# FPGA_PWR.net
KiCad netlist of a schematic drawn in Altium Designer
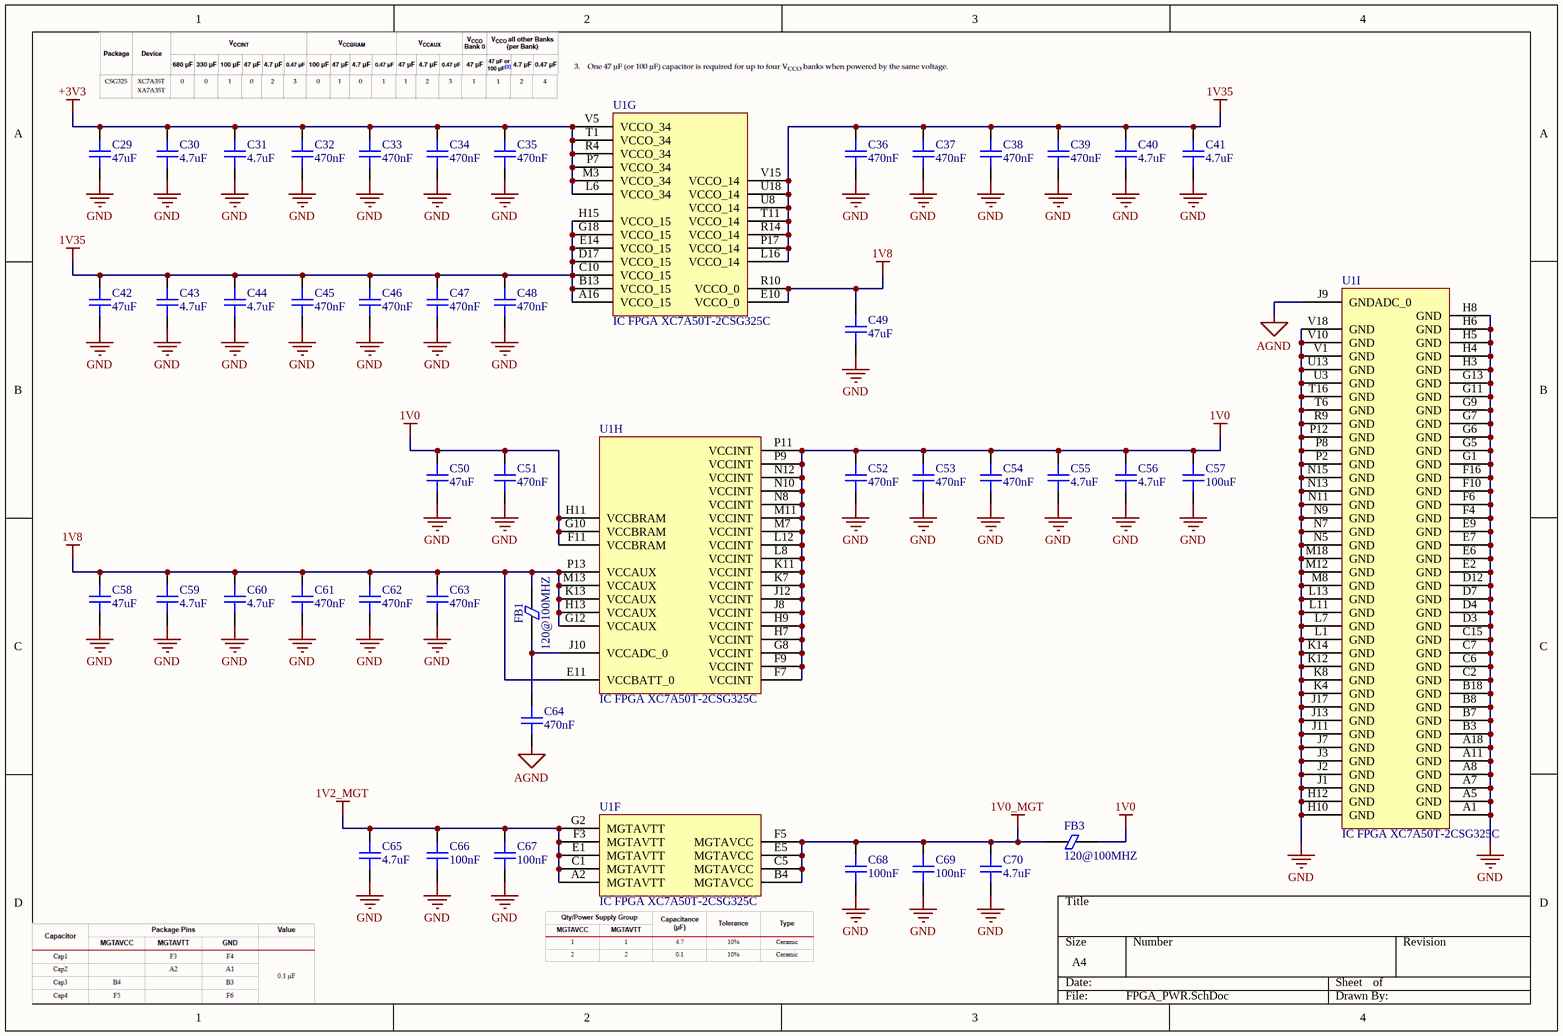
[diagram p0: FPGA_PWR.SchDoc]

(export (version "E")
  (design (tool "Eeschema 10.0.6"))
  (components
    (comp (ref "C29")
      (value "47uF")
      (footprint "GEN_C_0805")
      (fields
        (field (name "HOUSE PART NUMBER") "C-47uF-0805-002")
        (field (name "MANUFACTURER") "Samsung")
        (field (name "MANUFACTURER PART NUMBER") "CL21A476MQYNNNE")
      )
      (libsource (lib "DSO") (part "CAP 47uF 6.3V X5R 0805"))
    )
    (comp (ref "C30")
      (value "4.7uF")
      (footprint "GEN_C_0402")
      (fields
        (field (name "HOUSE PART NUMBER") "C-4.7uF-0402-002")
        (field (name "MANUFACTURER") "Murata")
        (field (name "MANUFACTURER PART NUMBER") "GRM155R60J475ME47D")
      )
      (libsource (lib "DSO") (part "CAP 4.7uF 6.3V X5R 0402"))
    )
    (comp (ref "C31")
      (value "4.7uF")
      (footprint "GEN_C_0402")
      (fields
        (field (name "HOUSE PART NUMBER") "C-4.7uF-0402-002")
        (field (name "MANUFACTURER") "Murata")
        (field (name "MANUFACTURER PART NUMBER") "GRM155R60J475ME47D")
      )
      (libsource (lib "DSO") (part "CAP 4.7uF 6.3V X5R 0402"))
    )
    (comp (ref "C32")
      (value "470nF")
      (footprint "GEN_C_0201")
      (fields
        (field (name "HOUSE PART NUMBER") "C-470nF-0201-002")
        (field (name "MANUFACTURER") "Murata")
        (field (name "MANUFACTURER PART NUMBER") "GRM033R60J474KE90D")
      )
      (libsource (lib "DSO") (part "CAP 470nF 6.3V X5R 0201"))
    )
    (comp (ref "C33")
      (value "470nF")
      (footprint "GEN_C_0201")
      (fields
        (field (name "HOUSE PART NUMBER") "C-470nF-0201-002")
        (field (name "MANUFACTURER") "Murata")
        (field (name "MANUFACTURER PART NUMBER") "GRM033R60J474KE90D")
      )
      (libsource (lib "DSO") (part "CAP 470nF 6.3V X5R 0201"))
    )
    (comp (ref "C34")
      (value "470nF")
      (footprint "GEN_C_0201")
      (fields
        (field (name "HOUSE PART NUMBER") "C-470nF-0201-002")
        (field (name "MANUFACTURER") "Murata")
        (field (name "MANUFACTURER PART NUMBER") "GRM033R60J474KE90D")
      )
      (libsource (lib "DSO") (part "CAP 470nF 6.3V X5R 0201"))
    )
    (comp (ref "C35")
      (value "470nF")
      (footprint "GEN_C_0201")
      (fields
        (field (name "HOUSE PART NUMBER") "C-470nF-0201-002")
        (field (name "MANUFACTURER") "Murata")
        (field (name "MANUFACTURER PART NUMBER") "GRM033R60J474KE90D")
      )
      (libsource (lib "DSO") (part "CAP 470nF 6.3V X5R 0201"))
    )
    (comp (ref "C36")
      (value "470nF")
      (footprint "GEN_C_0201")
      (fields
        (field (name "HOUSE PART NUMBER") "C-470nF-0201-002")
        (field (name "MANUFACTURER") "Murata")
        (field (name "MANUFACTURER PART NUMBER") "GRM033R60J474KE90D")
      )
      (libsource (lib "DSO") (part "CAP 470nF 6.3V X5R 0201"))
    )
    (comp (ref "C37")
      (value "470nF")
      (footprint "GEN_C_0201")
      (fields
        (field (name "HOUSE PART NUMBER") "C-470nF-0201-002")
        (field (name "MANUFACTURER") "Murata")
        (field (name "MANUFACTURER PART NUMBER") "GRM033R60J474KE90D")
      )
      (libsource (lib "DSO") (part "CAP 470nF 6.3V X5R 0201"))
    )
    (comp (ref "C38")
      (value "470nF")
      (footprint "GEN_C_0201")
      (fields
        (field (name "HOUSE PART NUMBER") "C-470nF-0201-002")
        (field (name "MANUFACTURER") "Murata")
        (field (name "MANUFACTURER PART NUMBER") "GRM033R60J474KE90D")
      )
      (libsource (lib "DSO") (part "CAP 470nF 6.3V X5R 0201"))
    )
    (comp (ref "C39")
      (value "470nF")
      (footprint "GEN_C_0201")
      (fields
        (field (name "HOUSE PART NUMBER") "C-470nF-0201-002")
        (field (name "MANUFACTURER") "Murata")
        (field (name "MANUFACTURER PART NUMBER") "GRM033R60J474KE90D")
      )
      (libsource (lib "DSO") (part "CAP 470nF 6.3V X5R 0201"))
    )
    (comp (ref "C40")
      (value "4.7uF")
      (footprint "GEN_C_0402")
      (fields
        (field (name "HOUSE PART NUMBER") "C-4.7uF-0402-002")
        (field (name "MANUFACTURER") "Murata")
        (field (name "MANUFACTURER PART NUMBER") "GRM155R60J475ME47D")
      )
      (libsource (lib "DSO") (part "CAP 4.7uF 6.3V X5R 0402"))
    )
    (comp (ref "C41")
      (value "4.7uF")
      (footprint "GEN_C_0402")
      (fields
        (field (name "HOUSE PART NUMBER") "C-4.7uF-0402-002")
        (field (name "MANUFACTURER") "Murata")
        (field (name "MANUFACTURER PART NUMBER") "GRM155R60J475ME47D")
      )
      (libsource (lib "DSO") (part "CAP 4.7uF 6.3V X5R 0402"))
    )
    (comp (ref "C42")
      (value "47uF")
      (footprint "GEN_C_0805")
      (fields
        (field (name "HOUSE PART NUMBER") "C-47uF-0805-002")
        (field (name "MANUFACTURER") "Samsung")
        (field (name "MANUFACTURER PART NUMBER") "CL21A476MQYNNNE")
      )
      (libsource (lib "DSO") (part "CAP 47uF 6.3V X5R 0805"))
    )
    (comp (ref "C43")
      (value "4.7uF")
      (footprint "GEN_C_0402")
      (fields
        (field (name "HOUSE PART NUMBER") "C-4.7uF-0402-002")
        (field (name "MANUFACTURER") "Murata")
        (field (name "MANUFACTURER PART NUMBER") "GRM155R60J475ME47D")
      )
      (libsource (lib "DSO") (part "CAP 4.7uF 6.3V X5R 0402"))
    )
    (comp (ref "C44")
      (value "4.7uF")
      (footprint "GEN_C_0402")
      (fields
        (field (name "HOUSE PART NUMBER") "C-4.7uF-0402-002")
        (field (name "MANUFACTURER") "Murata")
        (field (name "MANUFACTURER PART NUMBER") "GRM155R60J475ME47D")
      )
      (libsource (lib "DSO") (part "CAP 4.7uF 6.3V X5R 0402"))
    )
    (comp (ref "C45")
      (value "470nF")
      (footprint "GEN_C_0201")
      (fields
        (field (name "HOUSE PART NUMBER") "C-470nF-0201-002")
        (field (name "MANUFACTURER") "Murata")
        (field (name "MANUFACTURER PART NUMBER") "GRM033R60J474KE90D")
      )
      (libsource (lib "DSO") (part "CAP 470nF 6.3V X5R 0201"))
    )
    (comp (ref "C46")
      (value "470nF")
      (footprint "GEN_C_0201")
      (fields
        (field (name "HOUSE PART NUMBER") "C-470nF-0201-002")
        (field (name "MANUFACTURER") "Murata")
        (field (name "MANUFACTURER PART NUMBER") "GRM033R60J474KE90D")
      )
      (libsource (lib "DSO") (part "CAP 470nF 6.3V X5R 0201"))
    )
    (comp (ref "C47")
      (value "470nF")
      (footprint "GEN_C_0201")
      (fields
        (field (name "HOUSE PART NUMBER") "C-470nF-0201-002")
        (field (name "MANUFACTURER") "Murata")
        (field (name "MANUFACTURER PART NUMBER") "GRM033R60J474KE90D")
      )
      (libsource (lib "DSO") (part "CAP 470nF 6.3V X5R 0201"))
    )
    (comp (ref "C48")
      (value "470nF")
      (footprint "GEN_C_0201")
      (fields
        (field (name "HOUSE PART NUMBER") "C-470nF-0201-002")
        (field (name "MANUFACTURER") "Murata")
        (field (name "MANUFACTURER PART NUMBER") "GRM033R60J474KE90D")
      )
      (libsource (lib "DSO") (part "CAP 470nF 6.3V X5R 0201"))
    )
    (comp (ref "C49")
      (value "47uF")
      (footprint "GEN_C_0805")
      (fields
        (field (name "HOUSE PART NUMBER") "C-47uF-0805-002")
        (field (name "MANUFACTURER") "Samsung")
        (field (name "MANUFACTURER PART NUMBER") "CL21A476MQYNNNE")
      )
      (libsource (lib "DSO") (part "CAP 47uF 6.3V X5R 0805"))
    )
    (comp (ref "C50")
      (value "47uF")
      (footprint "GEN_C_0805")
      (fields
        (field (name "HOUSE PART NUMBER") "C-47uF-0805-002")
        (field (name "MANUFACTURER") "Samsung")
        (field (name "MANUFACTURER PART NUMBER") "CL21A476MQYNNNE")
      )
      (libsource (lib "DSO") (part "CAP 47uF 6.3V X5R 0805"))
    )
    (comp (ref "C51")
      (value "470nF")
      (footprint "GEN_C_0201")
      (fields
        (field (name "HOUSE PART NUMBER") "C-470nF-0201-002")
        (field (name "MANUFACTURER") "Murata")
        (field (name "MANUFACTURER PART NUMBER") "GRM033R60J474KE90D")
      )
      (libsource (lib "DSO") (part "CAP 470nF 6.3V X5R 0201"))
    )
    (comp (ref "C52")
      (value "470nF")
      (footprint "GEN_C_0201")
      (fields
        (field (name "HOUSE PART NUMBER") "C-470nF-0201-002")
        (field (name "MANUFACTURER") "Murata")
        (field (name "MANUFACTURER PART NUMBER") "GRM033R60J474KE90D")
      )
      (libsource (lib "DSO") (part "CAP 470nF 6.3V X5R 0201"))
    )
    (comp (ref "C53")
      (value "470nF")
      (footprint "GEN_C_0201")
      (fields
        (field (name "HOUSE PART NUMBER") "C-470nF-0201-002")
        (field (name "MANUFACTURER") "Murata")
        (field (name "MANUFACTURER PART NUMBER") "GRM033R60J474KE90D")
      )
      (libsource (lib "DSO") (part "CAP 470nF 6.3V X5R 0201"))
    )
    (comp (ref "C54")
      (value "470nF")
      (footprint "GEN_C_0201")
      (fields
        (field (name "HOUSE PART NUMBER") "C-470nF-0201-002")
        (field (name "MANUFACTURER") "Murata")
        (field (name "MANUFACTURER PART NUMBER") "GRM033R60J474KE90D")
      )
      (libsource (lib "DSO") (part "CAP 470nF 6.3V X5R 0201"))
    )
    (comp (ref "C55")
      (value "4.7uF")
      (footprint "GEN_C_0402")
      (fields
        (field (name "HOUSE PART NUMBER") "C-4.7uF-0402-002")
        (field (name "MANUFACTURER") "Murata")
        (field (name "MANUFACTURER PART NUMBER") "GRM155R60J475ME47D")
      )
      (libsource (lib "DSO") (part "CAP 4.7uF 6.3V X5R 0402"))
    )
    (comp (ref "C56")
      (value "4.7uF")
      (footprint "GEN_C_0402")
      (fields
        (field (name "HOUSE PART NUMBER") "C-4.7uF-0402-002")
        (field (name "MANUFACTURER") "Murata")
        (field (name "MANUFACTURER PART NUMBER") "GRM155R60J475ME47D")
      )
      (libsource (lib "DSO") (part "CAP 4.7uF 6.3V X5R 0402"))
    )
    (comp (ref "C57")
      (value "100uF")
      (footprint "GEN_C_1210")
      (fields
        (field (name "HOUSE PART NUMBER") "C-100uF-1210-002")
        (field (name "MANUFACTURER") "Samsung")
        (field (name "MANUFACTURER PART NUMBER") "CL32A107MQVNNNE")
      )
      (libsource (lib "DSO") (part "CAP 100uF 6.3V X5R 1210"))
    )
    (comp (ref "C58")
      (value "47uF")
      (footprint "GEN_C_0805")
      (fields
        (field (name "HOUSE PART NUMBER") "C-47uF-0805-002")
        (field (name "MANUFACTURER") "Samsung")
        (field (name "MANUFACTURER PART NUMBER") "CL21A476MQYNNNE")
      )
      (libsource (lib "DSO") (part "CAP 47uF 6.3V X5R 0805"))
    )
    (comp (ref "C59")
      (value "4.7uF")
      (footprint "GEN_C_0402")
      (fields
        (field (name "HOUSE PART NUMBER") "C-4.7uF-0402-002")
        (field (name "MANUFACTURER") "Murata")
        (field (name "MANUFACTURER PART NUMBER") "GRM155R60J475ME47D")
      )
      (libsource (lib "DSO") (part "CAP 4.7uF 6.3V X5R 0402"))
    )
    (comp (ref "C60")
      (value "4.7uF")
      (footprint "GEN_C_0402")
      (fields
        (field (name "HOUSE PART NUMBER") "C-4.7uF-0402-002")
        (field (name "MANUFACTURER") "Murata")
        (field (name "MANUFACTURER PART NUMBER") "GRM155R60J475ME47D")
      )
      (libsource (lib "DSO") (part "CAP 4.7uF 6.3V X5R 0402"))
    )
    (comp (ref "C61")
      (value "470nF")
      (footprint "GEN_C_0201")
      (fields
        (field (name "HOUSE PART NUMBER") "C-470nF-0201-002")
        (field (name "MANUFACTURER") "Murata")
        (field (name "MANUFACTURER PART NUMBER") "GRM033R60J474KE90D")
      )
      (libsource (lib "DSO") (part "CAP 470nF 6.3V X5R 0201"))
    )
    (comp (ref "C62")
      (value "470nF")
      (footprint "GEN_C_0201")
      (fields
        (field (name "HOUSE PART NUMBER") "C-470nF-0201-002")
        (field (name "MANUFACTURER") "Murata")
        (field (name "MANUFACTURER PART NUMBER") "GRM033R60J474KE90D")
      )
      (libsource (lib "DSO") (part "CAP 470nF 6.3V X5R 0201"))
    )
    (comp (ref "C63")
      (value "470nF")
      (footprint "GEN_C_0201")
      (fields
        (field (name "HOUSE PART NUMBER") "C-470nF-0201-002")
        (field (name "MANUFACTURER") "Murata")
        (field (name "MANUFACTURER PART NUMBER") "GRM033R60J474KE90D")
      )
      (libsource (lib "DSO") (part "CAP 470nF 6.3V X5R 0201"))
    )
    (comp (ref "C64")
      (value "470nF")
      (footprint "GEN_C_0201")
      (fields
        (field (name "HOUSE PART NUMBER") "C-470nF-0201-002")
        (field (name "MANUFACTURER") "Murata")
        (field (name "MANUFACTURER PART NUMBER") "GRM033R60J474KE90D")
      )
      (libsource (lib "DSO") (part "CAP 470nF 6.3V X5R 0201"))
    )
    (comp (ref "C65")
      (value "4.7uF")
      (footprint "GEN_C_0402")
      (fields
        (field (name "HOUSE PART NUMBER") "C-4.7uF-0402-002")
        (field (name "MANUFACTURER") "Murata")
        (field (name "MANUFACTURER PART NUMBER") "GRM155R60J475ME47D")
      )
      (libsource (lib "DSO") (part "CAP 4.7uF 6.3V X5R 0402"))
    )
    (comp (ref "C66")
      (value "100nF")
      (footprint "GEN_C_0201")
      (fields
        (field (name "HOUSE PART NUMBER") "C-100nF-0201-002")
        (field (name "MANUFACTURER") "Murata")
        (field (name "MANUFACTURER PART NUMBER") "GRM033R60J104KE19D")
      )
      (libsource (lib "DSO") (part "CAP 100nF 6.3V X5R 0201"))
    )
    (comp (ref "C67")
      (value "100nF")
      (footprint "GEN_C_0201")
      (fields
        (field (name "HOUSE PART NUMBER") "C-100nF-0201-002")
        (field (name "MANUFACTURER") "Murata")
        (field (name "MANUFACTURER PART NUMBER") "GRM033R60J104KE19D")
      )
      (libsource (lib "DSO") (part "CAP 100nF 6.3V X5R 0201"))
    )
    (comp (ref "C68")
      (value "100nF")
      (footprint "GEN_C_0201")
      (fields
        (field (name "HOUSE PART NUMBER") "C-100nF-0201-002")
        (field (name "MANUFACTURER") "Murata")
        (field (name "MANUFACTURER PART NUMBER") "GRM033R60J104KE19D")
      )
      (libsource (lib "DSO") (part "CAP 100nF 6.3V X5R 0201"))
    )
    (comp (ref "C69")
      (value "100nF")
      (footprint "GEN_C_0201")
      (fields
        (field (name "HOUSE PART NUMBER") "C-100nF-0201-002")
        (field (name "MANUFACTURER") "Murata")
        (field (name "MANUFACTURER PART NUMBER") "GRM033R60J104KE19D")
      )
      (libsource (lib "DSO") (part "CAP 100nF 6.3V X5R 0201"))
    )
    (comp (ref "C70")
      (value "4.7uF")
      (footprint "GEN_C_0402")
      (fields
        (field (name "HOUSE PART NUMBER") "C-4.7uF-0402-002")
        (field (name "MANUFACTURER") "Murata")
        (field (name "MANUFACTURER PART NUMBER") "GRM155R60J475ME47D")
      )
      (libsource (lib "DSO") (part "CAP 4.7uF 6.3V X5R 0402"))
    )
    (comp (ref "FB1")
      (value "120@100MHZ")
      (footprint "GEN_R_0402")
      (fields (field (name "HOUSE PART NUMBER") "BLM15PX121SN1D") (field (name "MANUFACTURER") "Murata"))
      (libsource (lib "DSO") (part "FERRITE BEAD 120 OHM 0402"))
    )
    (comp (ref "FB3")
      (value "120@100MHZ")
      (footprint "GEN_R_0402")
      (fields (field (name "HOUSE PART NUMBER") "BLM15PX121SN1D") (field (name "MANUFACTURER") "Murata"))
      (libsource (lib "DSO") (part "FERRITE BEAD 120 OHM 0402"))
    )
    (comp (ref "U1")
      (value "IC FPGA XC7A50T-2CSG325C")
      (footprint "XILINX_XC7A50T-2CSG325C")
      (description "Artix-7 FPGA, 150 User I/Os, 4 GTP, 324-Ball BGA, Speed Grade 2, Commercial Grade, Pb-Free")
      (fields (field (name "MANUFACTURER") "Xilinx") (field (name "HOUSE PART NUMBER") "XC7A50T-2CSG325C"))
      (libsource (lib "DSO") (part "IC FPGA XC7A50T-2CSG325C"))
    )
  )
  (nets
    (net (code "1") (name "+3V3") (class "Default")
      (node (ref "C29") (pin "2") (pinfunction "2_2") (pintype "passive"))
      (node (ref "C30") (pin "2") (pinfunction "2_2") (pintype "passive"))
      (node (ref "C31") (pin "2") (pinfunction "2_2") (pintype "passive"))
      (node (ref "C32") (pin "2") (pinfunction "2_2") (pintype "passive"))
      (node (ref "C33") (pin "2") (pinfunction "2_2") (pintype "passive"))
      (node (ref "C34") (pin "2") (pinfunction "2_2") (pintype "passive"))
      (node (ref "C35") (pin "2") (pinfunction "2_2") (pintype "passive"))
      (node (ref "U1") (pin "L6") (pinfunction "VCCO_34_L6") (pintype "power_in"))
      (node (ref "U1") (pin "M3") (pinfunction "VCCO_34_M3") (pintype "power_in"))
      (node (ref "U1") (pin "P7") (pinfunction "VCCO_34_P7") (pintype "power_in"))
      (node (ref "U1") (pin "R4") (pinfunction "VCCO_34_R4") (pintype "power_in"))
      (node (ref "U1") (pin "T1") (pinfunction "VCCO_34_T1") (pintype "power_in"))
      (node (ref "U1") (pin "V5") (pinfunction "VCCO_34_V5") (pintype "power_in"))
    )
    (net (code "2") (name "1V0") (class "Default")
      (node (ref "C50") (pin "2") (pinfunction "2_2") (pintype "passive"))
      (node (ref "C51") (pin "2") (pinfunction "2_2") (pintype "passive"))
      (node (ref "C52") (pin "2") (pinfunction "2_2") (pintype "passive"))
      (node (ref "C53") (pin "2") (pinfunction "2_2") (pintype "passive"))
      (node (ref "C54") (pin "2") (pinfunction "2_2") (pintype "passive"))
      (node (ref "C55") (pin "2") (pinfunction "2_2") (pintype "passive"))
      (node (ref "C56") (pin "2") (pinfunction "2_2") (pintype "passive"))
      (node (ref "C57") (pin "2") (pinfunction "2_2") (pintype "passive"))
      (node (ref "FB3") (pin "1") (pinfunction "1_1") (pintype "passive"))
      (node (ref "U1") (pin "F11") (pinfunction "VCCBRAM_F11") (pintype "power_in"))
      (node (ref "U1") (pin "F7") (pinfunction "VCCINT_F7") (pintype "power_in"))
      (node (ref "U1") (pin "F9") (pinfunction "VCCINT_F9") (pintype "power_in"))
      (node (ref "U1") (pin "G10") (pinfunction "VCCBRAM_G10") (pintype "power_in"))
      (node (ref "U1") (pin "G8") (pinfunction "VCCINT_G8") (pintype "power_in"))
      (node (ref "U1") (pin "H11") (pinfunction "VCCBRAM_H11") (pintype "power_in"))
      (node (ref "U1") (pin "H7") (pinfunction "VCCINT_H7") (pintype "power_in"))
      (node (ref "U1") (pin "H9") (pinfunction "VCCINT_H9") (pintype "power_in"))
      (node (ref "U1") (pin "J12") (pinfunction "VCCINT_J12") (pintype "power_in"))
      (node (ref "U1") (pin "J8") (pinfunction "VCCINT_J8") (pintype "power_in"))
      (node (ref "U1") (pin "K11") (pinfunction "VCCINT_K11") (pintype "power_in"))
      (node (ref "U1") (pin "K7") (pinfunction "VCCINT_K7") (pintype "power_in"))
      (node (ref "U1") (pin "L12") (pinfunction "VCCINT_L12") (pintype "power_in"))
      (node (ref "U1") (pin "L8") (pinfunction "VCCINT_L8") (pintype "power_in"))
      (node (ref "U1") (pin "M11") (pinfunction "VCCINT_M11") (pintype "power_in"))
      (node (ref "U1") (pin "M7") (pinfunction "VCCINT_M7") (pintype "power_in"))
      (node (ref "U1") (pin "N10") (pinfunction "VCCINT_N10") (pintype "power_in"))
      (node (ref "U1") (pin "N12") (pinfunction "VCCINT_N12") (pintype "power_in"))
      (node (ref "U1") (pin "N8") (pinfunction "VCCINT_N8") (pintype "power_in"))
      (node (ref "U1") (pin "P11") (pinfunction "VCCINT_P11") (pintype "power_in"))
      (node (ref "U1") (pin "P9") (pinfunction "VCCINT_P9") (pintype "power_in"))
    )
    (net (code "3") (name "1V0_MGT") (class "Default")
      (node (ref "C68") (pin "2") (pinfunction "2_2") (pintype "passive"))
      (node (ref "C69") (pin "2") (pinfunction "2_2") (pintype "passive"))
      (node (ref "C70") (pin "2") (pinfunction "2_2") (pintype "passive"))
      (node (ref "FB3") (pin "2") (pinfunction "2_2") (pintype "passive"))
      (node (ref "U1") (pin "B4") (pinfunction "MGTAVCC_B4") (pintype "power_in"))
      (node (ref "U1") (pin "C5") (pinfunction "MGTAVCC_C5") (pintype "power_in"))
      (node (ref "U1") (pin "E5") (pinfunction "MGTAVCC_E5") (pintype "power_in"))
      (node (ref "U1") (pin "F5") (pinfunction "MGTAVCC_F5") (pintype "power_in"))
    )
    (net (code "4") (name "1V2_MGT") (class "Default")
      (node (ref "C65") (pin "2") (pinfunction "2_2") (pintype "passive"))
      (node (ref "C66") (pin "2") (pinfunction "2_2") (pintype "passive"))
      (node (ref "C67") (pin "2") (pinfunction "2_2") (pintype "passive"))
      (node (ref "U1") (pin "A2") (pinfunction "MGTAVTT_A2") (pintype "power_in"))
      (node (ref "U1") (pin "C1") (pinfunction "MGTAVTT_C1") (pintype "power_in"))
      (node (ref "U1") (pin "E1") (pinfunction "MGTAVTT_E1") (pintype "power_in"))
      (node (ref "U1") (pin "F3") (pinfunction "MGTAVTT_F3") (pintype "power_in"))
      (node (ref "U1") (pin "G2") (pinfunction "MGTAVTT_G2") (pintype "power_in"))
    )
    (net (code "5") (name "1V8") (class "Default")
      (node (ref "C49") (pin "2") (pinfunction "2_2") (pintype "passive"))
      (node (ref "C58") (pin "2") (pinfunction "2_2") (pintype "passive"))
      (node (ref "C59") (pin "2") (pinfunction "2_2") (pintype "passive"))
      (node (ref "C60") (pin "2") (pinfunction "2_2") (pintype "passive"))
      (node (ref "C61") (pin "2") (pinfunction "2_2") (pintype "passive"))
      (node (ref "C62") (pin "2") (pinfunction "2_2") (pintype "passive"))
      (node (ref "C63") (pin "2") (pinfunction "2_2") (pintype "passive"))
      (node (ref "FB1") (pin "2") (pinfunction "2_2") (pintype "passive"))
      (node (ref "U1") (pin "E10") (pinfunction "VCCO_0_E10") (pintype "power_in"))
      (node (ref "U1") (pin "E11") (pinfunction "VCCBATT_0_E11") (pintype "power_in"))
      (node (ref "U1") (pin "G12") (pinfunction "VCCAUX_G12") (pintype "power_in"))
      (node (ref "U1") (pin "H13") (pinfunction "VCCAUX_H13") (pintype "power_in"))
      (node (ref "U1") (pin "K13") (pinfunction "VCCAUX_K13") (pintype "power_in"))
      (node (ref "U1") (pin "M13") (pinfunction "VCCAUX_M13") (pintype "power_in"))
      (node (ref "U1") (pin "P13") (pinfunction "VCCAUX_P13") (pintype "power_in"))
      (node (ref "U1") (pin "R10") (pinfunction "VCCO_0_R10") (pintype "power_in"))
    )
    (net (code "6") (name "1V35") (class "Default")
      (node (ref "C36") (pin "2") (pinfunction "2_2") (pintype "passive"))
      (node (ref "C37") (pin "2") (pinfunction "2_2") (pintype "passive"))
      (node (ref "C38") (pin "2") (pinfunction "2_2") (pintype "passive"))
      (node (ref "C39") (pin "2") (pinfunction "2_2") (pintype "passive"))
      (node (ref "C40") (pin "2") (pinfunction "2_2") (pintype "passive"))
      (node (ref "C41") (pin "2") (pinfunction "2_2") (pintype "passive"))
      (node (ref "C42") (pin "2") (pinfunction "2_2") (pintype "passive"))
      (node (ref "C43") (pin "2") (pinfunction "2_2") (pintype "passive"))
      (node (ref "C44") (pin "2") (pinfunction "2_2") (pintype "passive"))
      (node (ref "C45") (pin "2") (pinfunction "2_2") (pintype "passive"))
      (node (ref "C46") (pin "2") (pinfunction "2_2") (pintype "passive"))
      (node (ref "C47") (pin "2") (pinfunction "2_2") (pintype "passive"))
      (node (ref "C48") (pin "2") (pinfunction "2_2") (pintype "passive"))
      (node (ref "U1") (pin "A16") (pinfunction "VCCO_15_A16") (pintype "power_in"))
      (node (ref "U1") (pin "B13") (pinfunction "VCCO_15_B13") (pintype "power_in"))
      (node (ref "U1") (pin "C10") (pinfunction "VCCO_15_C10") (pintype "power_in"))
      (node (ref "U1") (pin "D17") (pinfunction "VCCO_15_D17") (pintype "power_in"))
      (node (ref "U1") (pin "E14") (pinfunction "VCCO_15_E14") (pintype "power_in"))
      (node (ref "U1") (pin "G18") (pinfunction "VCCO_15_G18") (pintype "power_in"))
      (node (ref "U1") (pin "H15") (pinfunction "VCCO_15_H15") (pintype "power_in"))
      (node (ref "U1") (pin "L16") (pinfunction "VCCO_14_L16") (pintype "power_in"))
      (node (ref "U1") (pin "P17") (pinfunction "VCCO_14_P17") (pintype "power_in"))
      (node (ref "U1") (pin "R14") (pinfunction "VCCO_14_R14") (pintype "power_in"))
      (node (ref "U1") (pin "T11") (pinfunction "VCCO_14_T11") (pintype "power_in"))
      (node (ref "U1") (pin "U18") (pinfunction "VCCO_14_U18") (pintype "power_in"))
      (node (ref "U1") (pin "U8") (pinfunction "VCCO_14_U8") (pintype "power_in"))
      (node (ref "U1") (pin "V15") (pinfunction "VCCO_14_V15") (pintype "power_in"))
    )
    (net (code "7") (name "AGND") (class "Default")
      (node (ref "C64") (pin "1") (pinfunction "1_1") (pintype "passive"))
      (node (ref "U1") (pin "J9") (pinfunction "GNDADC_0_J9") (pintype "power_in"))
    )
    (net (code "8") (name "GND") (class "Default")
      (node (ref "C29") (pin "1") (pinfunction "1_1") (pintype "passive"))
      (node (ref "C30") (pin "1") (pinfunction "1_1") (pintype "passive"))
      (node (ref "C31") (pin "1") (pinfunction "1_1") (pintype "passive"))
      (node (ref "C32") (pin "1") (pinfunction "1_1") (pintype "passive"))
      (node (ref "C33") (pin "1") (pinfunction "1_1") (pintype "passive"))
      (node (ref "C34") (pin "1") (pinfunction "1_1") (pintype "passive"))
      (node (ref "C35") (pin "1") (pinfunction "1_1") (pintype "passive"))
      (node (ref "C36") (pin "1") (pinfunction "1_1") (pintype "passive"))
      (node (ref "C37") (pin "1") (pinfunction "1_1") (pintype "passive"))
      (node (ref "C38") (pin "1") (pinfunction "1_1") (pintype "passive"))
      (node (ref "C39") (pin "1") (pinfunction "1_1") (pintype "passive"))
      (node (ref "C40") (pin "1") (pinfunction "1_1") (pintype "passive"))
      (node (ref "C41") (pin "1") (pinfunction "1_1") (pintype "passive"))
      (node (ref "C42") (pin "1") (pinfunction "1_1") (pintype "passive"))
      (node (ref "C43") (pin "1") (pinfunction "1_1") (pintype "passive"))
      (node (ref "C44") (pin "1") (pinfunction "1_1") (pintype "passive"))
      (node (ref "C45") (pin "1") (pinfunction "1_1") (pintype "passive"))
      (node (ref "C46") (pin "1") (pinfunction "1_1") (pintype "passive"))
      (node (ref "C47") (pin "1") (pinfunction "1_1") (pintype "passive"))
      (node (ref "C48") (pin "1") (pinfunction "1_1") (pintype "passive"))
      (node (ref "C49") (pin "1") (pinfunction "1_1") (pintype "passive"))
      (node (ref "C50") (pin "1") (pinfunction "1_1") (pintype "passive"))
      (node (ref "C51") (pin "1") (pinfunction "1_1") (pintype "passive"))
      (node (ref "C52") (pin "1") (pinfunction "1_1") (pintype "passive"))
      (node (ref "C53") (pin "1") (pinfunction "1_1") (pintype "passive"))
      (node (ref "C54") (pin "1") (pinfunction "1_1") (pintype "passive"))
      (node (ref "C55") (pin "1") (pinfunction "1_1") (pintype "passive"))
      (node (ref "C56") (pin "1") (pinfunction "1_1") (pintype "passive"))
      (node (ref "C57") (pin "1") (pinfunction "1_1") (pintype "passive"))
      (node (ref "C58") (pin "1") (pinfunction "1_1") (pintype "passive"))
      (node (ref "C59") (pin "1") (pinfunction "1_1") (pintype "passive"))
      (node (ref "C60") (pin "1") (pinfunction "1_1") (pintype "passive"))
      (node (ref "C61") (pin "1") (pinfunction "1_1") (pintype "passive"))
      (node (ref "C62") (pin "1") (pinfunction "1_1") (pintype "passive"))
      (node (ref "C63") (pin "1") (pinfunction "1_1") (pintype "passive"))
      (node (ref "C65") (pin "1") (pinfunction "1_1") (pintype "passive"))
      (node (ref "C66") (pin "1") (pinfunction "1_1") (pintype "passive"))
      (node (ref "C67") (pin "1") (pinfunction "1_1") (pintype "passive"))
      (node (ref "C68") (pin "1") (pinfunction "1_1") (pintype "passive"))
      (node (ref "C69") (pin "1") (pinfunction "1_1") (pintype "passive"))
      (node (ref "C70") (pin "1") (pinfunction "1_1") (pintype "passive"))
      (node (ref "U1") (pin "A1") (pinfunction "GND_A1") (pintype "power_in"))
      (node (ref "U1") (pin "A11") (pinfunction "GND_A11") (pintype "power_in"))
      (node (ref "U1") (pin "A18") (pinfunction "GND_A18") (pintype "power_in"))
      (node (ref "U1") (pin "A5") (pinfunction "GND_A5") (pintype "power_in"))
      (node (ref "U1") (pin "A7") (pinfunction "GND_A7") (pintype "power_in"))
      (node (ref "U1") (pin "A8") (pinfunction "GND_A8") (pintype "power_in"))
      (node (ref "U1") (pin "B18") (pinfunction "GND_B18") (pintype "power_in"))
      (node (ref "U1") (pin "B3") (pinfunction "GND_B3") (pintype "power_in"))
      (node (ref "U1") (pin "B7") (pinfunction "GND_B7") (pintype "power_in"))
      (node (ref "U1") (pin "B8") (pinfunction "GND_B8") (pintype "power_in"))
      (node (ref "U1") (pin "C15") (pinfunction "GND_C15") (pintype "power_in"))
      (node (ref "U1") (pin "C2") (pinfunction "GND_C2") (pintype "power_in"))
      (node (ref "U1") (pin "C6") (pinfunction "GND_C6") (pintype "power_in"))
      (node (ref "U1") (pin "C7") (pinfunction "GND_C7") (pintype "power_in"))
      (node (ref "U1") (pin "D12") (pinfunction "GND_D12") (pintype "power_in"))
      (node (ref "U1") (pin "D3") (pinfunction "GND_D3") (pintype "power_in"))
      (node (ref "U1") (pin "D4") (pinfunction "GND_D4") (pintype "power_in"))
      (node (ref "U1") (pin "D7") (pinfunction "GND_D7") (pintype "power_in"))
      (node (ref "U1") (pin "E2") (pinfunction "GND_E2") (pintype "power_in"))
      (node (ref "U1") (pin "E6") (pinfunction "GND_E6") (pintype "power_in"))
      (node (ref "U1") (pin "E7") (pinfunction "GND_E7") (pintype "power_in"))
      (node (ref "U1") (pin "E9") (pinfunction "GND_E9") (pintype "power_in"))
      (node (ref "U1") (pin "F10") (pinfunction "GND_F10") (pintype "power_in"))
      (node (ref "U1") (pin "F16") (pinfunction "GND_F16") (pintype "power_in"))
      (node (ref "U1") (pin "F4") (pinfunction "GND_F4") (pintype "power_in"))
      (node (ref "U1") (pin "F6") (pinfunction "GND_F6") (pintype "power_in"))
      (node (ref "U1") (pin "G1") (pinfunction "GND_G1") (pintype "power_in"))
      (node (ref "U1") (pin "G11") (pinfunction "GND_G11") (pintype "power_in"))
      (node (ref "U1") (pin "G13") (pinfunction "GND_G13") (pintype "power_in"))
      (node (ref "U1") (pin "G5") (pinfunction "GND_G5") (pintype "power_in"))
      (node (ref "U1") (pin "G6") (pinfunction "GND_G6") (pintype "power_in"))
      (node (ref "U1") (pin "G7") (pinfunction "GND_G7") (pintype "power_in"))
      (node (ref "U1") (pin "G9") (pinfunction "GND_G9") (pintype "power_in"))
      (node (ref "U1") (pin "H10") (pinfunction "GND_H10") (pintype "power_in"))
      (node (ref "U1") (pin "H12") (pinfunction "GND_H12") (pintype "power_in"))
      (node (ref "U1") (pin "H3") (pinfunction "GND_H3") (pintype "power_in"))
      (node (ref "U1") (pin "H4") (pinfunction "GND_H4") (pintype "power_in"))
      (node (ref "U1") (pin "H5") (pinfunction "GND_H5") (pintype "power_in"))
      (node (ref "U1") (pin "H6") (pinfunction "GND_H6") (pintype "power_in"))
      (node (ref "U1") (pin "H8") (pinfunction "GND_H8") (pintype "power_in"))
      (node (ref "U1") (pin "J1") (pinfunction "GND_J1") (pintype "power_in"))
      (node (ref "U1") (pin "J11") (pinfunction "GND_J11") (pintype "power_in"))
      (node (ref "U1") (pin "J13") (pinfunction "GND_J13") (pintype "power_in"))
      (node (ref "U1") (pin "J17") (pinfunction "GND_J17") (pintype "power_in"))
      (node (ref "U1") (pin "J2") (pinfunction "GND_J2") (pintype "power_in"))
      (node (ref "U1") (pin "J3") (pinfunction "GND_J3") (pintype "power_in"))
      (node (ref "U1") (pin "J7") (pinfunction "GND_J7") (pintype "power_in"))
      (node (ref "U1") (pin "K12") (pinfunction "GND_K12") (pintype "power_in"))
      (node (ref "U1") (pin "K14") (pinfunction "GND_K14") (pintype "power_in"))
      (node (ref "U1") (pin "K4") (pinfunction "GND_K4") (pintype "power_in"))
      (node (ref "U1") (pin "K8") (pinfunction "GND_K8") (pintype "power_in"))
      (node (ref "U1") (pin "L1") (pinfunction "GND_L1") (pintype "power_in"))
      (node (ref "U1") (pin "L11") (pinfunction "GND_L11") (pintype "power_in"))
      (node (ref "U1") (pin "L13") (pinfunction "GND_L13") (pintype "power_in"))
      (node (ref "U1") (pin "L7") (pinfunction "GND_L7") (pintype "power_in"))
      (node (ref "U1") (pin "M12") (pinfunction "GND_M12") (pintype "power_in"))
      (node (ref "U1") (pin "M18") (pinfunction "GND_M18") (pintype "power_in"))
      (node (ref "U1") (pin "M8") (pinfunction "GND_M8") (pintype "power_in"))
      (node (ref "U1") (pin "N11") (pinfunction "GND_N11") (pintype "power_in"))
      (node (ref "U1") (pin "N13") (pinfunction "GND_N13") (pintype "power_in"))
      (node (ref "U1") (pin "N15") (pinfunction "GND_N15") (pintype "power_in"))
      (node (ref "U1") (pin "N5") (pinfunction "GND_N5") (pintype "power_in"))
      (node (ref "U1") (pin "N7") (pinfunction "GND_N7") (pintype "power_in"))
      (node (ref "U1") (pin "N9") (pinfunction "GND_N9") (pintype "power_in"))
      (node (ref "U1") (pin "P12") (pinfunction "GND_P12") (pintype "power_in"))
      (node (ref "U1") (pin "P2") (pinfunction "GND_P2") (pintype "power_in"))
      (node (ref "U1") (pin "P8") (pinfunction "GND_P8") (pintype "power_in"))
      (node (ref "U1") (pin "R9") (pinfunction "GND_R9") (pintype "power_in"))
      (node (ref "U1") (pin "T16") (pinfunction "GND_T16") (pintype "power_in"))
      (node (ref "U1") (pin "T6") (pinfunction "GND_T6") (pintype "power_in"))
      (node (ref "U1") (pin "U13") (pinfunction "GND_U13") (pintype "power_in"))
      (node (ref "U1") (pin "U3") (pinfunction "GND_U3") (pintype "power_in"))
      (node (ref "U1") (pin "V1") (pinfunction "GND_V1") (pintype "power_in"))
      (node (ref "U1") (pin "V10") (pinfunction "GND_V10") (pintype "power_in"))
      (node (ref "U1") (pin "V18") (pinfunction "GND_V18") (pintype "power_in"))
    )
    (net (code "9") (name "Net-(U1H-VCCADC_0)") (class "Default")
      (node (ref "C64") (pin "2") (pinfunction "2_2") (pintype "passive"))
      (node (ref "FB1") (pin "1") (pinfunction "1_1") (pintype "passive"))
      (node (ref "U1") (pin "J10") (pinfunction "VCCADC_0_J10") (pintype "power_in"))
    )
  )
)
